# FT4232.net
KiCad netlist of a schematic drawn in Altium Designer
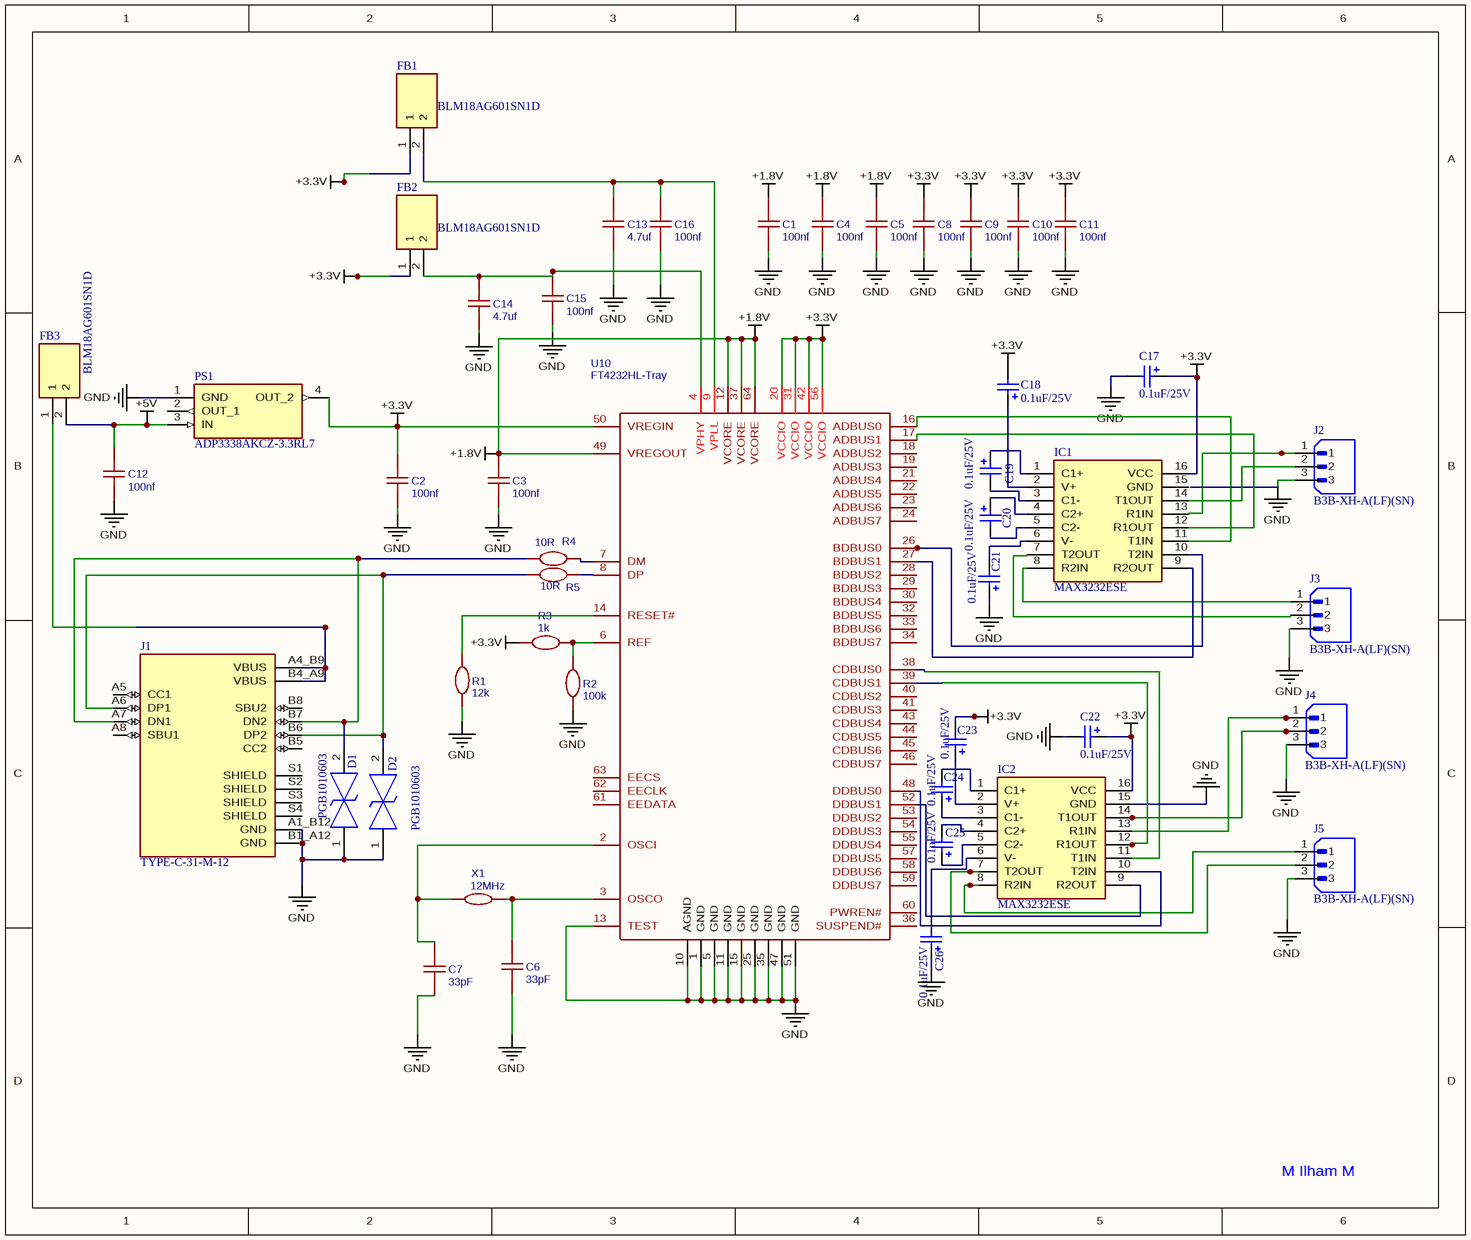
[diagram p0: FT4232.schdoc]

(export (version "E")
  (design (tool "Eeschema 10.0.6"))
  (components
    (comp (ref "C1")
      (value "100nf")
      (footprint "1608_[0603] Capacitor")
      (fields (field (name "CONTRIBUTOR") "LCEDA_Lib"))
      (libsource (lib "altium-import") (part "root_3_100nf_"))
    )
    (comp (ref "C2")
      (value "100nf")
      (footprint "1608_[0603] Capacitor")
      (fields (field (name "CONTRIBUTOR") "LCEDA_Lib"))
      (libsource (lib "altium-import") (part "root_3_100nf_"))
    )
    (comp (ref "C3")
      (value "100nf")
      (footprint "1608_[0603] Capacitor")
      (fields (field (name "CONTRIBUTOR") "LCEDA_Lib"))
      (libsource (lib "altium-import") (part "root_3_100nf_"))
    )
    (comp (ref "C4")
      (value "100nf")
      (footprint "1608_[0603] Capacitor")
      (fields (field (name "CONTRIBUTOR") "LCEDA_Lib"))
      (libsource (lib "altium-import") (part "root_3_100nf_"))
    )
    (comp (ref "C5")
      (value "100nf")
      (footprint "1608_[0603] Capacitor")
      (fields (field (name "CONTRIBUTOR") "LCEDA_Lib"))
      (libsource (lib "altium-import") (part "root_3_100nf_"))
    )
    (comp (ref "C6")
      (value "33pF")
      (footprint "1608_[0603] Capacitor")
      (fields (field (name "CONTRIBUTOR") "LCEDA_Lib"))
      (libsource (lib "altium-import") (part "root_3_100nf_"))
    )
    (comp (ref "C7")
      (value "33pF")
      (footprint "1608_[0603] Capacitor")
      (fields (field (name "CONTRIBUTOR") "LCEDA_Lib"))
      (libsource (lib "altium-import") (part "root_3_100nf_"))
    )
    (comp (ref "C8")
      (value "100nf")
      (footprint "1608_[0603] Capacitor")
      (fields (field (name "CONTRIBUTOR") "LCEDA_Lib"))
      (libsource (lib "altium-import") (part "root_3_100nf_"))
    )
    (comp (ref "C9")
      (value "100nf")
      (footprint "1608_[0603] Capacitor")
      (fields (field (name "CONTRIBUTOR") "LCEDA_Lib"))
      (libsource (lib "altium-import") (part "root_3_100nf_"))
    )
    (comp (ref "C10")
      (value "100nf")
      (footprint "1608_[0603] Capacitor")
      (fields (field (name "CONTRIBUTOR") "LCEDA_Lib"))
      (libsource (lib "altium-import") (part "root_3_100nf_"))
    )
    (comp (ref "C11")
      (value "100nf")
      (footprint "1608_[0603] Capacitor")
      (fields (field (name "CONTRIBUTOR") "LCEDA_Lib"))
      (libsource (lib "altium-import") (part "root_3_100nf_"))
    )
    (comp (ref "C12")
      (value "100nf")
      (footprint "1608_[0603] Capacitor")
      (fields (field (name "CONTRIBUTOR") "LCEDA_Lib"))
      (libsource (lib "altium-import") (part "root_3_100nf_"))
    )
    (comp (ref "C13")
      (value "4.7uf")
      (footprint "1608_[0603] Capacitor")
      (fields (field (name "CONTRIBUTOR") "LCEDA_Lib"))
      (libsource (lib "altium-import") (part "root_3_4.7uf_"))
    )
    (comp (ref "C14")
      (value "4.7uf")
      (footprint "1608_[0603] Capacitor")
      (fields (field (name "CONTRIBUTOR") "LCEDA_Lib"))
      (libsource (lib "altium-import") (part "root_3_4.7uf_"))
    )
    (comp (ref "C15")
      (value "100nf")
      (footprint "1608_[0603] Capacitor")
      (fields (field (name "CONTRIBUTOR") "LCEDA_Lib"))
      (libsource (lib "altium-import") (part "root_3_100nf_"))
    )
    (comp (ref "C16")
      (value "100nf")
      (footprint "1608_[0603] Capacitor")
      (fields (field (name "CONTRIBUTOR") "LCEDA_Lib"))
      (libsource (lib "altium-import") (part "root_3_100nf_"))
    )
    (comp (ref "C17")
      (value "0.1uF/25V")
      (footprint "1608_[0603] Capacitor")
      (description "0603 SMD Tantalum Capacitor")
      (libsource (lib "MCD_TOOLS") (part "Cap_1uF_POL_10%_TANA"))
    )
    (comp (ref "C18")
      (value "0.1uF/25V")
      (footprint "1608_[0603] Capacitor")
      (description "0603 SMD Tantalum Capacitor")
      (libsource (lib "MCD_TOOLS") (part "Cap_1uF_POL_10%_TANA"))
    )
    (comp (ref "C19")
      (value "0.1uF/25V")
      (footprint "1608_[0603] Capacitor")
      (description "0603 SMD Tantalum Capacitor")
      (libsource (lib "MCD_TOOLS") (part "Cap_1uF_POL_10%_TANA"))
    )
    (comp (ref "C20")
      (value "0.1uF/25V")
      (footprint "1608_[0603] Capacitor")
      (description "0603 SMD Tantalum Capacitor")
      (libsource (lib "MCD_TOOLS") (part "Cap_1uF_POL_10%_TANA"))
    )
    (comp (ref "C21")
      (value "0.1uF/25V")
      (footprint "1608_[0603] Capacitor")
      (description "0603 SMD Tantalum Capacitor")
      (libsource (lib "MCD_TOOLS") (part "Cap_1uF_POL_10%_TANA"))
    )
    (comp (ref "C22")
      (value "0.1uF/25V")
      (footprint "1608_[0603] Capacitor")
      (description "0603 SMD Tantalum Capacitor")
      (libsource (lib "MCD_TOOLS") (part "Cap_1uF_POL_10%_TANA"))
    )
    (comp (ref "C23")
      (value "0.1uF/25V")
      (footprint "1608_[0603] Capacitor")
      (description "0603 SMD Tantalum Capacitor")
      (libsource (lib "MCD_TOOLS") (part "Cap_1uF_POL_10%_TANA"))
    )
    (comp (ref "C24")
      (value "0.1uF/25V")
      (footprint "1608_[0603] Capacitor")
      (description "0603 SMD Tantalum Capacitor")
      (libsource (lib "MCD_TOOLS") (part "Cap_1uF_POL_10%_TANA"))
    )
    (comp (ref "C25")
      (value "0.1uF/25V")
      (footprint "1608_[0603] Capacitor")
      (description "0603 SMD Tantalum Capacitor")
      (libsource (lib "MCD_TOOLS") (part "Cap_1uF_POL_10%_TANA"))
    )
    (comp (ref "C26")
      (value "0.1uF/25V")
      (footprint "1608_[0603] Capacitor")
      (description "0603 SMD Tantalum Capacitor")
      (libsource (lib "MCD_TOOLS") (part "Cap_1uF_POL_10%_TANA"))
    )
    (comp (ref "D1")
      (value "PGB1010603")
      (footprint "SamacSys:PGB1010603NRHF")
      (description "TVS Diode (Bi-directional)")
      (libsource (lib "*") (part "PGB1010603"))
    )
    (comp (ref "D2")
      (value "PGB1010603")
      (footprint "SamacSys:PGB1010603NRHF")
      (description "TVS Diode (Bi-directional)")
      (libsource (lib "*") (part "PGB1010603"))
    )
    (comp (ref "FB1")
      (value "BLM18AG601SN1D")
      (footprint "SamacSys:BLM18SP221SN1B")
      (description "Ferrite Bead")
      (fields (field (name "MOUSER PART NUMBER") "81-BLM11A601S"))
      (libsource (lib "*") (part "BLM18AG601SN1D"))
    )
    (comp (ref "FB2")
      (value "BLM18AG601SN1D")
      (footprint "SamacSys:BLM18SP221SN1B")
      (description "Ferrite Bead")
      (fields (field (name "MOUSER PART NUMBER") "81-BLM11A601S"))
      (libsource (lib "*") (part "BLM18AG601SN1D"))
    )
    (comp (ref "FB3")
      (value "BLM18AG601SN1D")
      (footprint "SamacSys:BLM18SP221SN1B")
      (description "Ferrite Bead")
      (fields (field (name "MOUSER PART NUMBER") "81-BLM11A601S"))
      (libsource (lib "*") (part "BLM18AG601SN1D"))
    )
    (comp (ref "IC1")
      (value "MAX3232ESE")
      (footprint "SamacSys:SOIC127P600X175-16N")
      (description "Integrated Circuit")
      (fields
        (field (name "MANUFACTURER_PART_NUMBER") "MAX232EESE+T")
        (field (name "MOUSER PART NUMBER") "700-MAX232EESET")
      )
      (libsource (lib "*") (part "MAX232EESE+T"))
    )
    (comp (ref "IC2")
      (value "MAX3232ESE")
      (footprint "SamacSys:SOIC127P600X175-16N")
      (description "Integrated Circuit")
      (fields
        (field (name "MANUFACTURER_PART_NUMBER") "MAX232EESE+T")
        (field (name "MOUSER PART NUMBER") "700-MAX232EESET")
      )
      (libsource (lib "*") (part "MAX232EESE+T"))
    )
    (comp (ref "J1")
      (value "TYPE-C-31-M-12")
      (footprint "HRO_TYPE-C-31-M-12")
      (description "USB Connectors 24 Receptacle 1 8.94*7.3mm RoHS")
      (fields (field (name "MF") "HRO Electronics Co., Ltd."))
      (libsource (lib "KS_ALT_V1") (part "TYPE-C-31-M-12"))
    )
    (comp (ref "J2")
      (value "B3B-XH-A(LF)(SN)")
      (footprint "JST_B3B-XH-A(LF)(SN)")
      (description "Connector Header Through Hole 3 position 0.098 (2.50mm)")
      (fields (field (name "MF") "JST Sales"))
      (libsource (lib "KS_ALT_V1") (part "B3B-XH-A(LF)(SN)"))
    )
    (comp (ref "J3")
      (value "B3B-XH-A(LF)(SN)")
      (footprint "JST_B3B-XH-A(LF)(SN)")
      (description "Connector Header Through Hole 3 position 0.098 (2.50mm)")
      (fields (field (name "MF") "JST Sales"))
      (libsource (lib "KS_ALT_V1") (part "B3B-XH-A(LF)(SN)"))
    )
    (comp (ref "J4")
      (value "B3B-XH-A(LF)(SN)")
      (footprint "JST_B3B-XH-A(LF)(SN)")
      (description "Connector Header Through Hole 3 position 0.098 (2.50mm)")
      (fields (field (name "MF") "JST Sales"))
      (libsource (lib "KS_ALT_V1") (part "B3B-XH-A(LF)(SN)"))
    )
    (comp (ref "J5")
      (value "B3B-XH-A(LF)(SN)")
      (footprint "JST_B3B-XH-A(LF)(SN)")
      (description "Connector Header Through Hole 3 position 0.098 (2.50mm)")
      (fields (field (name "MF") "JST Sales"))
      (libsource (lib "KS_ALT_V1") (part "B3B-XH-A(LF)(SN)"))
    )
    (comp (ref "PS1")
      (value "ADP3338AKCZ-3.3RL7")
      (footprint "SamacSys:SOT230P700X180-4N")
      (description "Power Supply")
      (fields (field (name "MOUSER PART NUMBER") "584-ADP3338AKCZ3.3R7"))
      (libsource (lib "*") (part "ADP3338AKCZ-3.3RL7"))
    )
    (comp (ref "R1")
      (value "12k")
      (footprint "1608_[0603] Resistor")
      (fields (field (name "CONTRIBUTOR") "LCEDA_Lib"))
      (libsource (lib "altium-import") (part "root_3_12k_"))
    )
    (comp (ref "R2")
      (value "100k")
      (footprint "1608_[0603] Resistor")
      (fields (field (name "CONTRIBUTOR") "LCEDA_Lib"))
      (libsource (lib "altium-import") (part "root_3_100k_"))
    )
    (comp (ref "R3")
      (value "1k")
      (footprint "1608_[0603] Resistor")
      (fields (field (name "CONTRIBUTOR") "LCEDA_Lib"))
      (libsource (lib "altium-import") (part "root_0_1k_"))
    )
    (comp (ref "R4")
      (value "10R")
      (footprint "1608_[0603] Resistor")
      (fields (field (name "CONTRIBUTOR") "LCEDA_Lib"))
      (libsource (lib "altium-import") (part "root_0_100k_"))
    )
    (comp (ref "R5")
      (value "10R")
      (footprint "1608_[0603] Resistor")
      (fields (field (name "CONTRIBUTOR") "LCEDA_Lib"))
      (libsource (lib "altium-import") (part "root_0_100k_"))
    )
    (comp (ref "U10")
      (value "FT4232HL-Tray")
      (footprint "QFP50P1200X1200X160-64N")
      (libsource (lib "altium-import") (part "root_0_FT4232HL-Tray_"))
    )
    (comp (ref "X1")
      (value "12MHz")
      (footprint "X TAL")
      (fields
        (field (name "MANUFACTURER") "CTS(西迪斯)")
        (field (name "MANUFACTURER PART") "ATS240CSM-1E")
        (field (name "CONTRIBUTOR") "LCSC")
      )
      (libsource (lib "altium-import") (part "root_0_12MHz_"))
    )
  )
  (nets
    (net (code "1") (name "+1.8V") (class "Default")
      (node (ref "C1") (pin "1") (pinfunction "1_1") (pintype "passive"))
      (node (ref "C3") (pin "1") (pinfunction "1_1") (pintype "passive"))
      (node (ref "C4") (pin "1") (pinfunction "1_1") (pintype "passive"))
      (node (ref "C5") (pin "1") (pinfunction "1_1") (pintype "passive"))
      (node (ref "U10") (pin "12") (pinfunction "VCORE_12") (pintype "passive"))
      (node (ref "U10") (pin "37") (pinfunction "VCORE_37") (pintype "passive"))
      (node (ref "U10") (pin "49") (pinfunction "VREGOUT_49") (pintype "passive"))
      (node (ref "U10") (pin "64") (pinfunction "VCORE_64") (pintype "passive"))
    )
    (net (code "2") (name "+3.3V") (class "Default")
      (node (ref "C10") (pin "1") (pinfunction "1_1") (pintype "passive"))
      (node (ref "C11") (pin "1") (pinfunction "1_1") (pintype "passive"))
      (node (ref "C17") (pin "1") (pinfunction "1_1") (pintype "passive"))
      (node (ref "C18") (pin "2") (pinfunction "2_2") (pintype "passive"))
      (node (ref "C2") (pin "1") (pinfunction "1_1") (pintype "passive"))
      (node (ref "C22") (pin "1") (pinfunction "1_1") (pintype "passive"))
      (node (ref "C23") (pin "2") (pinfunction "2_2") (pintype "passive"))
      (node (ref "C8") (pin "1") (pinfunction "1_1") (pintype "passive"))
      (node (ref "C9") (pin "1") (pinfunction "1_1") (pintype "passive"))
      (node (ref "FB1") (pin "1") (pinfunction "1_1") (pintype "passive"))
      (node (ref "FB2") (pin "1") (pinfunction "1_1") (pintype "passive"))
      (node (ref "IC1") (pin "16") (pinfunction "VCC_16") (pintype "passive"))
      (node (ref "IC2") (pin "16") (pinfunction "VCC_16") (pintype "passive"))
      (node (ref "PS1") (pin "4") (pinfunction "OUT_2_4") (pintype "output"))
      (node (ref "R3") (pin "1") (pinfunction "1_1") (pintype "passive"))
      (node (ref "U10") (pin "20") (pinfunction "VCCIO_20") (pintype "passive"))
      (node (ref "U10") (pin "31") (pinfunction "VCCIO_31") (pintype "passive"))
      (node (ref "U10") (pin "42") (pinfunction "VCCIO_42") (pintype "passive"))
      (node (ref "U10") (pin "50") (pinfunction "VREGIN_50") (pintype "passive"))
      (node (ref "U10") (pin "56") (pinfunction "VCCIO_56") (pintype "passive"))
    )
    (net (code "3") (name "+5V") (class "Default")
      (node (ref "C12") (pin "1") (pinfunction "1_1") (pintype "passive"))
      (node (ref "FB3") (pin "2") (pinfunction "2_2") (pintype "passive"))
      (node (ref "PS1") (pin "3") (pinfunction "IN_3") (pintype "input"))
    )
    (net (code "4") (name "GND") (class "Default")
      (node (ref "C1") (pin "2") (pinfunction "2_2") (pintype "passive"))
      (node (ref "C10") (pin "2") (pinfunction "2_2") (pintype "passive"))
      (node (ref "C11") (pin "2") (pinfunction "2_2") (pintype "passive"))
      (node (ref "C12") (pin "2") (pinfunction "2_2") (pintype "passive"))
      (node (ref "C13") (pin "2") (pinfunction "2_2") (pintype "passive"))
      (node (ref "C14") (pin "2") (pinfunction "2_2") (pintype "passive"))
      (node (ref "C15") (pin "2") (pinfunction "2_2") (pintype "passive"))
      (node (ref "C16") (pin "2") (pinfunction "2_2") (pintype "passive"))
      (node (ref "C17") (pin "2") (pinfunction "2_2") (pintype "passive"))
      (node (ref "C2") (pin "2") (pinfunction "2_2") (pintype "passive"))
      (node (ref "C21") (pin "1") (pinfunction "1_1") (pintype "passive"))
      (node (ref "C22") (pin "2") (pinfunction "2_2") (pintype "passive"))
      (node (ref "C26") (pin "1") (pinfunction "1_1") (pintype "passive"))
      (node (ref "C3") (pin "2") (pinfunction "2_2") (pintype "passive"))
      (node (ref "C4") (pin "2") (pinfunction "2_2") (pintype "passive"))
      (node (ref "C5") (pin "2") (pinfunction "2_2") (pintype "passive"))
      (node (ref "C6") (pin "2") (pinfunction "2_2") (pintype "passive"))
      (node (ref "C7") (pin "2") (pinfunction "2_2") (pintype "passive"))
      (node (ref "C8") (pin "2") (pinfunction "2_2") (pintype "passive"))
      (node (ref "C9") (pin "2") (pinfunction "2_2") (pintype "passive"))
      (node (ref "D1") (pin "1") (pinfunction "1_1") (pintype "passive"))
      (node (ref "D2") (pin "1") (pinfunction "1_1") (pintype "passive"))
      (node (ref "IC2") (pin "15") (pinfunction "GND_15") (pintype "passive"))
      (node (ref "J1") (pin "A1_B12") (pinfunction "GND_A1_B12") (pintype "power_in"))
      (node (ref "J1") (pin "B1_A12") (pinfunction "GND_B1_A12") (pintype "power_in"))
      (node (ref "J2") (pin "3") (pinfunction "3_3") (pintype "passive"))
      (node (ref "J3") (pin "3") (pinfunction "3_3") (pintype "passive"))
      (node (ref "J4") (pin "3") (pinfunction "3_3") (pintype "passive"))
      (node (ref "J5") (pin "3") (pinfunction "3_3") (pintype "passive"))
      (node (ref "PS1") (pin "1") (pinfunction "GND_1") (pintype "power_in"))
      (node (ref "R1") (pin "2") (pinfunction "2_2") (pintype "passive"))
      (node (ref "R2") (pin "2") (pinfunction "2_2") (pintype "passive"))
      (node (ref "U10") (pin "1") (pinfunction "GND_1") (pintype "passive"))
      (node (ref "U10") (pin "10") (pinfunction "AGND_10") (pintype "passive"))
      (node (ref "U10") (pin "11") (pinfunction "GND_11") (pintype "passive"))
      (node (ref "U10") (pin "13") (pinfunction "TEST_13") (pintype "passive"))
      (node (ref "U10") (pin "15") (pinfunction "GND_15") (pintype "passive"))
      (node (ref "U10") (pin "25") (pinfunction "GND_25") (pintype "passive"))
      (node (ref "U10") (pin "35") (pinfunction "GND_35") (pintype "passive"))
      (node (ref "U10") (pin "47") (pinfunction "GND_47") (pintype "passive"))
      (node (ref "U10") (pin "5") (pinfunction "GND_5") (pintype "passive"))
      (node (ref "U10") (pin "51") (pinfunction "GND_51") (pintype "passive"))
    )
    (net (code "5") (name "Net-(FB3-Pad1)") (class "Default")
      (node (ref "FB3") (pin "1") (pinfunction "1_1") (pintype "passive"))
      (node (ref "J1") (pin "A4_B9") (pinfunction "VBUS_A4_B9") (pintype "power_in"))
      (node (ref "J1") (pin "B4_A9") (pinfunction "VBUS_B4_A9") (pintype "power_in"))
    )
    (net (code "6") (name "Net-(IC1-C1+)") (class "Default")
      (node (ref "C19") (pin "1") (pinfunction "1_1") (pintype "passive"))
      (node (ref "IC1") (pin "1") (pinfunction "C1+_1") (pintype "passive"))
    )
    (net (code "7") (name "Net-(IC1-C1-)") (class "Default")
      (node (ref "C19") (pin "2") (pinfunction "2_2") (pintype "passive"))
      (node (ref "IC1") (pin "3") (pinfunction "C1-_3") (pintype "passive"))
    )
    (net (code "8") (name "Net-(IC1-C2+)") (class "Default")
      (node (ref "C20") (pin "1") (pinfunction "1_1") (pintype "passive"))
      (node (ref "IC1") (pin "4") (pinfunction "C2+_4") (pintype "passive"))
    )
    (net (code "9") (name "Net-(IC1-C2-)") (class "Default")
      (node (ref "C20") (pin "2") (pinfunction "2_2") (pintype "passive"))
      (node (ref "IC1") (pin "5") (pinfunction "C2-_5") (pintype "passive"))
    )
    (net (code "10") (name "Net-(IC1-R1IN)") (class "Default")
      (node (ref "IC1") (pin "13") (pinfunction "R1IN_13") (pintype "passive"))
      (node (ref "J2") (pin "1") (pinfunction "1_1") (pintype "passive"))
    )
    (net (code "11") (name "Net-(IC1-R1OUT)") (class "Default")
      (node (ref "IC1") (pin "12") (pinfunction "R1OUT_12") (pintype "passive"))
      (node (ref "U10") (pin "17") (pinfunction "ADBUS1_17") (pintype "passive"))
    )
    (net (code "12") (name "Net-(IC1-R2IN)") (class "Default")
      (node (ref "IC1") (pin "8") (pinfunction "R2IN_8") (pintype "passive"))
      (node (ref "J3") (pin "1") (pinfunction "1_1") (pintype "passive"))
    )
    (net (code "13") (name "Net-(IC1-R2OUT)") (class "Default")
      (node (ref "IC1") (pin "9") (pinfunction "R2OUT_9") (pintype "passive"))
      (node (ref "U10") (pin "27") (pinfunction "BDBUS1_27") (pintype "passive"))
    )
    (net (code "14") (name "Net-(IC1-T1IN)") (class "Default")
      (node (ref "IC1") (pin "11") (pinfunction "T1IN_11") (pintype "passive"))
      (node (ref "U10") (pin "16") (pinfunction "ADBUS0_16") (pintype "passive"))
    )
    (net (code "15") (name "Net-(IC1-T1OUT)") (class "Default")
      (node (ref "IC1") (pin "14") (pinfunction "T1OUT_14") (pintype "passive"))
      (node (ref "J2") (pin "2") (pinfunction "2_2") (pintype "passive"))
    )
    (net (code "16") (name "Net-(IC1-T2IN)") (class "Default")
      (node (ref "IC1") (pin "10") (pinfunction "T2IN_10") (pintype "passive"))
      (node (ref "U10") (pin "26") (pinfunction "BDBUS0_26") (pintype "passive"))
    )
    (net (code "17") (name "Net-(IC1-T2OUT)") (class "Default")
      (node (ref "IC1") (pin "7") (pinfunction "T2OUT_7") (pintype "passive"))
      (node (ref "J3") (pin "2") (pinfunction "2_2") (pintype "passive"))
    )
    (net (code "18") (name "Net-(IC1-V+)") (class "Default")
      (node (ref "C18") (pin "1") (pinfunction "1_1") (pintype "passive"))
      (node (ref "IC1") (pin "2") (pinfunction "V+_2") (pintype "passive"))
    )
    (net (code "19") (name "Net-(IC1-V-)") (class "Default")
      (node (ref "C21") (pin "2") (pinfunction "2_2") (pintype "passive"))
      (node (ref "IC1") (pin "6") (pinfunction "V-_6") (pintype "passive"))
    )
    (net (code "20") (name "Net-(IC2-C1+)") (class "Default")
      (node (ref "C24") (pin "2") (pinfunction "2_2") (pintype "passive"))
      (node (ref "IC2") (pin "1") (pinfunction "C1+_1") (pintype "passive"))
    )
    (net (code "21") (name "Net-(IC2-C1-)") (class "Default")
      (node (ref "C24") (pin "1") (pinfunction "1_1") (pintype "passive"))
      (node (ref "IC2") (pin "3") (pinfunction "C1-_3") (pintype "passive"))
    )
    (net (code "22") (name "Net-(IC2-C2+)") (class "Default")
      (node (ref "C25") (pin "2") (pinfunction "2_2") (pintype "passive"))
      (node (ref "IC2") (pin "4") (pinfunction "C2+_4") (pintype "passive"))
    )
    (net (code "23") (name "Net-(IC2-C2-)") (class "Default")
      (node (ref "C25") (pin "1") (pinfunction "1_1") (pintype "passive"))
      (node (ref "IC2") (pin "5") (pinfunction "C2-_5") (pintype "passive"))
    )
    (net (code "24") (name "Net-(IC2-R1IN)") (class "Default")
      (node (ref "IC2") (pin "13") (pinfunction "R1IN_13") (pintype "passive"))
      (node (ref "J4") (pin "1") (pinfunction "1_1") (pintype "passive"))
    )
    (net (code "25") (name "Net-(IC2-R1OUT)") (class "Default")
      (node (ref "IC2") (pin "12") (pinfunction "R1OUT_12") (pintype "passive"))
      (node (ref "U10") (pin "39") (pinfunction "CDBUS1_39") (pintype "passive"))
    )
    (net (code "26") (name "Net-(IC2-R2IN)") (class "Default")
      (node (ref "IC2") (pin "8") (pinfunction "R2IN_8") (pintype "passive"))
      (node (ref "J5") (pin "1") (pinfunction "1_1") (pintype "passive"))
    )
    (net (code "27") (name "Net-(IC2-R2OUT)") (class "Default")
      (node (ref "IC2") (pin "9") (pinfunction "R2OUT_9") (pintype "passive"))
      (node (ref "U10") (pin "52") (pinfunction "DDBUS1_52") (pintype "passive"))
    )
    (net (code "28") (name "Net-(IC2-T1IN)") (class "Default")
      (node (ref "IC2") (pin "11") (pinfunction "T1IN_11") (pintype "passive"))
      (node (ref "U10") (pin "38") (pinfunction "CDBUS0_38") (pintype "passive"))
    )
    (net (code "29") (name "Net-(IC2-T1OUT)") (class "Default")
      (node (ref "IC2") (pin "14") (pinfunction "T1OUT_14") (pintype "passive"))
      (node (ref "J4") (pin "2") (pinfunction "2_2") (pintype "passive"))
    )
    (net (code "30") (name "Net-(IC2-T2IN)") (class "Default")
      (node (ref "IC2") (pin "10") (pinfunction "T2IN_10") (pintype "passive"))
      (node (ref "U10") (pin "48") (pinfunction "DDBUS0_48") (pintype "passive"))
    )
    (net (code "31") (name "Net-(IC2-T2OUT)") (class "Default")
      (node (ref "IC2") (pin "7") (pinfunction "T2OUT_7") (pintype "passive"))
      (node (ref "J5") (pin "2") (pinfunction "2_2") (pintype "passive"))
    )
    (net (code "32") (name "Net-(IC2-V+)") (class "Default")
      (node (ref "C23") (pin "1") (pinfunction "1_1") (pintype "passive"))
      (node (ref "IC2") (pin "2") (pinfunction "V+_2") (pintype "passive"))
    )
    (net (code "33") (name "Net-(IC2-V-)") (class "Default")
      (node (ref "C26") (pin "2") (pinfunction "2_2") (pintype "passive"))
      (node (ref "IC2") (pin "6") (pinfunction "V-_6") (pintype "passive"))
    )
    (net (code "34") (name "Net-(J1-DN1)") (class "Default")
      (node (ref "D1") (pin "2") (pinfunction "2_2") (pintype "passive"))
      (node (ref "J1") (pin "A7") (pinfunction "DN1_A7") (pintype "bidirectional"))
      (node (ref "J1") (pin "B7") (pinfunction "DN2_B7") (pintype "bidirectional"))
      (node (ref "R4") (pin "1") (pinfunction "1_1") (pintype "passive"))
    )
    (net (code "35") (name "Net-(J1-DP1)") (class "Default")
      (node (ref "D2") (pin "2") (pinfunction "2_2") (pintype "passive"))
      (node (ref "J1") (pin "A6") (pinfunction "DP1_A6") (pintype "bidirectional"))
      (node (ref "J1") (pin "B6") (pinfunction "DP2_B6") (pintype "bidirectional"))
      (node (ref "R5") (pin "1") (pinfunction "1_1") (pintype "passive"))
    )
    (net (code "36") (name "Net-(U10-DM)") (class "Default")
      (node (ref "R4") (pin "2") (pinfunction "2_2") (pintype "passive"))
      (node (ref "U10") (pin "7") (pinfunction "DM_7") (pintype "passive"))
    )
    (net (code "37") (name "Net-(U10-DP)") (class "Default")
      (node (ref "R5") (pin "2") (pinfunction "2_2") (pintype "passive"))
      (node (ref "U10") (pin "8") (pinfunction "DP_8") (pintype "passive"))
    )
    (net (code "38") (name "Net-(U10-OSCI)") (class "Default")
      (node (ref "C7") (pin "1") (pinfunction "1_1") (pintype "passive"))
      (node (ref "U10") (pin "2") (pinfunction "OSCI_2") (pintype "passive"))
      (node (ref "X1") (pin "1") (pinfunction "1_1") (pintype "passive"))
    )
    (net (code "39") (name "Net-(U10-OSCO)") (class "Default")
      (node (ref "C6") (pin "1") (pinfunction "1_1") (pintype "passive"))
      (node (ref "U10") (pin "3") (pinfunction "OSCO_3") (pintype "passive"))
      (node (ref "X1") (pin "2") (pinfunction "2_2") (pintype "passive"))
    )
    (net (code "40") (name "Net-(U10-REF)") (class "Default")
      (node (ref "R2") (pin "1") (pinfunction "1_1") (pintype "passive"))
      (node (ref "R3") (pin "2") (pinfunction "2_2") (pintype "passive"))
      (node (ref "U10") (pin "6") (pinfunction "REF_6") (pintype "passive"))
    )
    (net (code "41") (name "Net-(U10-RESET#)") (class "Default")
      (node (ref "R1") (pin "1") (pinfunction "1_1") (pintype "passive"))
      (node (ref "U10") (pin "14") (pinfunction "RESET#_14") (pintype "passive"))
    )
    (net (code "42") (name "Net-(U10-VPHY)") (class "Default")
      (node (ref "C14") (pin "1") (pinfunction "1_1") (pintype "passive"))
      (node (ref "C15") (pin "1") (pinfunction "1_1") (pintype "passive"))
      (node (ref "FB2") (pin "2") (pinfunction "2_2") (pintype "passive"))
      (node (ref "U10") (pin "4") (pinfunction "VPHY_4") (pintype "passive"))
    )
    (net (code "43") (name "Net-(U10-VPLL)") (class "Default")
      (node (ref "C13") (pin "1") (pinfunction "1_1") (pintype "passive"))
      (node (ref "C16") (pin "1") (pinfunction "1_1") (pintype "passive"))
      (node (ref "FB1") (pin "2") (pinfunction "2_2") (pintype "passive"))
      (node (ref "U10") (pin "9") (pinfunction "VPLL_9") (pintype "passive"))
    )
    (net (code "44") (name "unconnected-(IC1-GND-Pad15)") (class "Default")
      (node (ref "IC1") (pin "15") (pinfunction "GND_15") (pintype "passive"))
    )
    (net (code "45") (name "unconnected-(J1-CC1-PadA5)") (class "Default")
      (node (ref "J1") (pin "A5") (pinfunction "CC1_A5") (pintype "bidirectional"))
    )
    (net (code "46") (name "unconnected-(J1-CC2-PadB5)") (class "Default")
      (node (ref "J1") (pin "B5") (pinfunction "CC2_B5") (pintype "bidirectional"))
    )
    (net (code "47") (name "unconnected-(J1-SBU1-PadA8)") (class "Default")
      (node (ref "J1") (pin "A8") (pinfunction "SBU1_A8") (pintype "bidirectional"))
    )
    (net (code "48") (name "unconnected-(J1-SBU2-PadB8)") (class "Default")
      (node (ref "J1") (pin "B8") (pinfunction "SBU2_B8") (pintype "bidirectional"))
    )
    (net (code "49") (name "unconnected-(J1-SHIELD-PadS1)") (class "Default")
      (node (ref "J1") (pin "S1") (pinfunction "SHIELD_S1") (pintype "passive"))
    )
    (net (code "50") (name "unconnected-(J1-SHIELD-PadS2)") (class "Default")
      (node (ref "J1") (pin "S2") (pinfunction "SHIELD_S2") (pintype "passive"))
    )
    (net (code "51") (name "unconnected-(J1-SHIELD-PadS3)") (class "Default")
      (node (ref "J1") (pin "S3") (pinfunction "SHIELD_S3") (pintype "passive"))
    )
    (net (code "52") (name "unconnected-(J1-SHIELD-PadS4)") (class "Default")
      (node (ref "J1") (pin "S4") (pinfunction "SHIELD_S4") (pintype "passive"))
    )
    (net (code "53") (name "unconnected-(PS1-OUT_1-Pad2)") (class "Default")
      (node (ref "PS1") (pin "2") (pinfunction "OUT_1_2") (pintype "output"))
    )
    (net (code "54") (name "unconnected-(U10-ADBUS2-Pad18)") (class "Default")
      (node (ref "U10") (pin "18") (pinfunction "ADBUS2_18") (pintype "passive"))
    )
    (net (code "55") (name "unconnected-(U10-ADBUS3-Pad19)") (class "Default")
      (node (ref "U10") (pin "19") (pinfunction "ADBUS3_19") (pintype "passive"))
    )
    (net (code "56") (name "unconnected-(U10-ADBUS4-Pad21)") (class "Default")
      (node (ref "U10") (pin "21") (pinfunction "ADBUS4_21") (pintype "passive"))
    )
    (net (code "57") (name "unconnected-(U10-ADBUS5-Pad22)") (class "Default")
      (node (ref "U10") (pin "22") (pinfunction "ADBUS5_22") (pintype "passive"))
    )
    (net (code "58") (name "unconnected-(U10-ADBUS6-Pad23)") (class "Default")
      (node (ref "U10") (pin "23") (pinfunction "ADBUS6_23") (pintype "passive"))
    )
    (net (code "59") (name "unconnected-(U10-ADBUS7-Pad24)") (class "Default")
      (node (ref "U10") (pin "24") (pinfunction "ADBUS7_24") (pintype "passive"))
    )
    (net (code "60") (name "unconnected-(U10-BDBUS2-Pad28)") (class "Default")
      (node (ref "U10") (pin "28") (pinfunction "BDBUS2_28") (pintype "passive"))
    )
    (net (code "61") (name "unconnected-(U10-BDBUS3-Pad29)") (class "Default")
      (node (ref "U10") (pin "29") (pinfunction "BDBUS3_29") (pintype "passive"))
    )
    (net (code "62") (name "unconnected-(U10-BDBUS4-Pad30)") (class "Default")
      (node (ref "U10") (pin "30") (pinfunction "BDBUS4_30") (pintype "passive"))
    )
    (net (code "63") (name "unconnected-(U10-BDBUS5-Pad32)") (class "Default")
      (node (ref "U10") (pin "32") (pinfunction "BDBUS5_32") (pintype "passive"))
    )
    (net (code "64") (name "unconnected-(U10-BDBUS6-Pad33)") (class "Default")
      (node (ref "U10") (pin "33") (pinfunction "BDBUS6_33") (pintype "passive"))
    )
    (net (code "65") (name "unconnected-(U10-BDBUS7-Pad34)") (class "Default")
      (node (ref "U10") (pin "34") (pinfunction "BDBUS7_34") (pintype "passive"))
    )
    (net (code "66") (name "unconnected-(U10-CDBUS2-Pad40)") (class "Default")
      (node (ref "U10") (pin "40") (pinfunction "CDBUS2_40") (pintype "passive"))
    )
    (net (code "67") (name "unconnected-(U10-CDBUS3-Pad41)") (class "Default")
      (node (ref "U10") (pin "41") (pinfunction "CDBUS3_41") (pintype "passive"))
    )
    (net (code "68") (name "unconnected-(U10-CDBUS4-Pad43)") (class "Default")
      (node (ref "U10") (pin "43") (pinfunction "CDBUS4_43") (pintype "passive"))
    )
    (net (code "69") (name "unconnected-(U10-CDBUS5-Pad44)") (class "Default")
      (node (ref "U10") (pin "44") (pinfunction "CDBUS5_44") (pintype "passive"))
    )
    (net (code "70") (name "unconnected-(U10-CDBUS6-Pad45)") (class "Default")
      (node (ref "U10") (pin "45") (pinfunction "CDBUS6_45") (pintype "passive"))
    )
    (net (code "71") (name "unconnected-(U10-CDBUS7-Pad46)") (class "Default")
      (node (ref "U10") (pin "46") (pinfunction "CDBUS7_46") (pintype "passive"))
    )
    (net (code "72") (name "unconnected-(U10-DDBUS2-Pad53)") (class "Default")
      (node (ref "U10") (pin "53") (pinfunction "DDBUS2_53") (pintype "passive"))
    )
    (net (code "73") (name "unconnected-(U10-DDBUS3-Pad54)") (class "Default")
      (node (ref "U10") (pin "54") (pinfunction "DDBUS3_54") (pintype "passive"))
    )
    (net (code "74") (name "unconnected-(U10-DDBUS4-Pad55)") (class "Default")
      (node (ref "U10") (pin "55") (pinfunction "DDBUS4_55") (pintype "passive"))
    )
    (net (code "75") (name "unconnected-(U10-DDBUS5-Pad57)") (class "Default")
      (node (ref "U10") (pin "57") (pinfunction "DDBUS5_57") (pintype "passive"))
    )
    (net (code "76") (name "unconnected-(U10-DDBUS6-Pad58)") (class "Default")
      (node (ref "U10") (pin "58") (pinfunction "DDBUS6_58") (pintype "passive"))
    )
    (net (code "77") (name "unconnected-(U10-DDBUS7-Pad59)") (class "Default")
      (node (ref "U10") (pin "59") (pinfunction "DDBUS7_59") (pintype "passive"))
    )
    (net (code "78") (name "unconnected-(U10-EECLK-Pad62)") (class "Default")
      (node (ref "U10") (pin "62") (pinfunction "EECLK_62") (pintype "passive"))
    )
    (net (code "79") (name "unconnected-(U10-EECS-Pad63)") (class "Default")
      (node (ref "U10") (pin "63") (pinfunction "EECS_63") (pintype "passive"))
    )
    (net (code "80") (name "unconnected-(U10-EEDATA-Pad61)") (class "Default")
      (node (ref "U10") (pin "61") (pinfunction "EEDATA_61") (pintype "passive"))
    )
    (net (code "81") (name "unconnected-(U10-PWREN#-Pad60)") (class "Default")
      (node (ref "U10") (pin "60") (pinfunction "PWREN#_60") (pintype "passive"))
    )
    (net (code "82") (name "unconnected-(U10-SUSPEND#-Pad36)") (class "Default")
      (node (ref "U10") (pin "36") (pinfunction "SUSPEND#_36") (pintype "passive"))
    )
  )
)
